# Controller_Sheet.net
KiCad netlist of a schematic drawn in Altium Designer
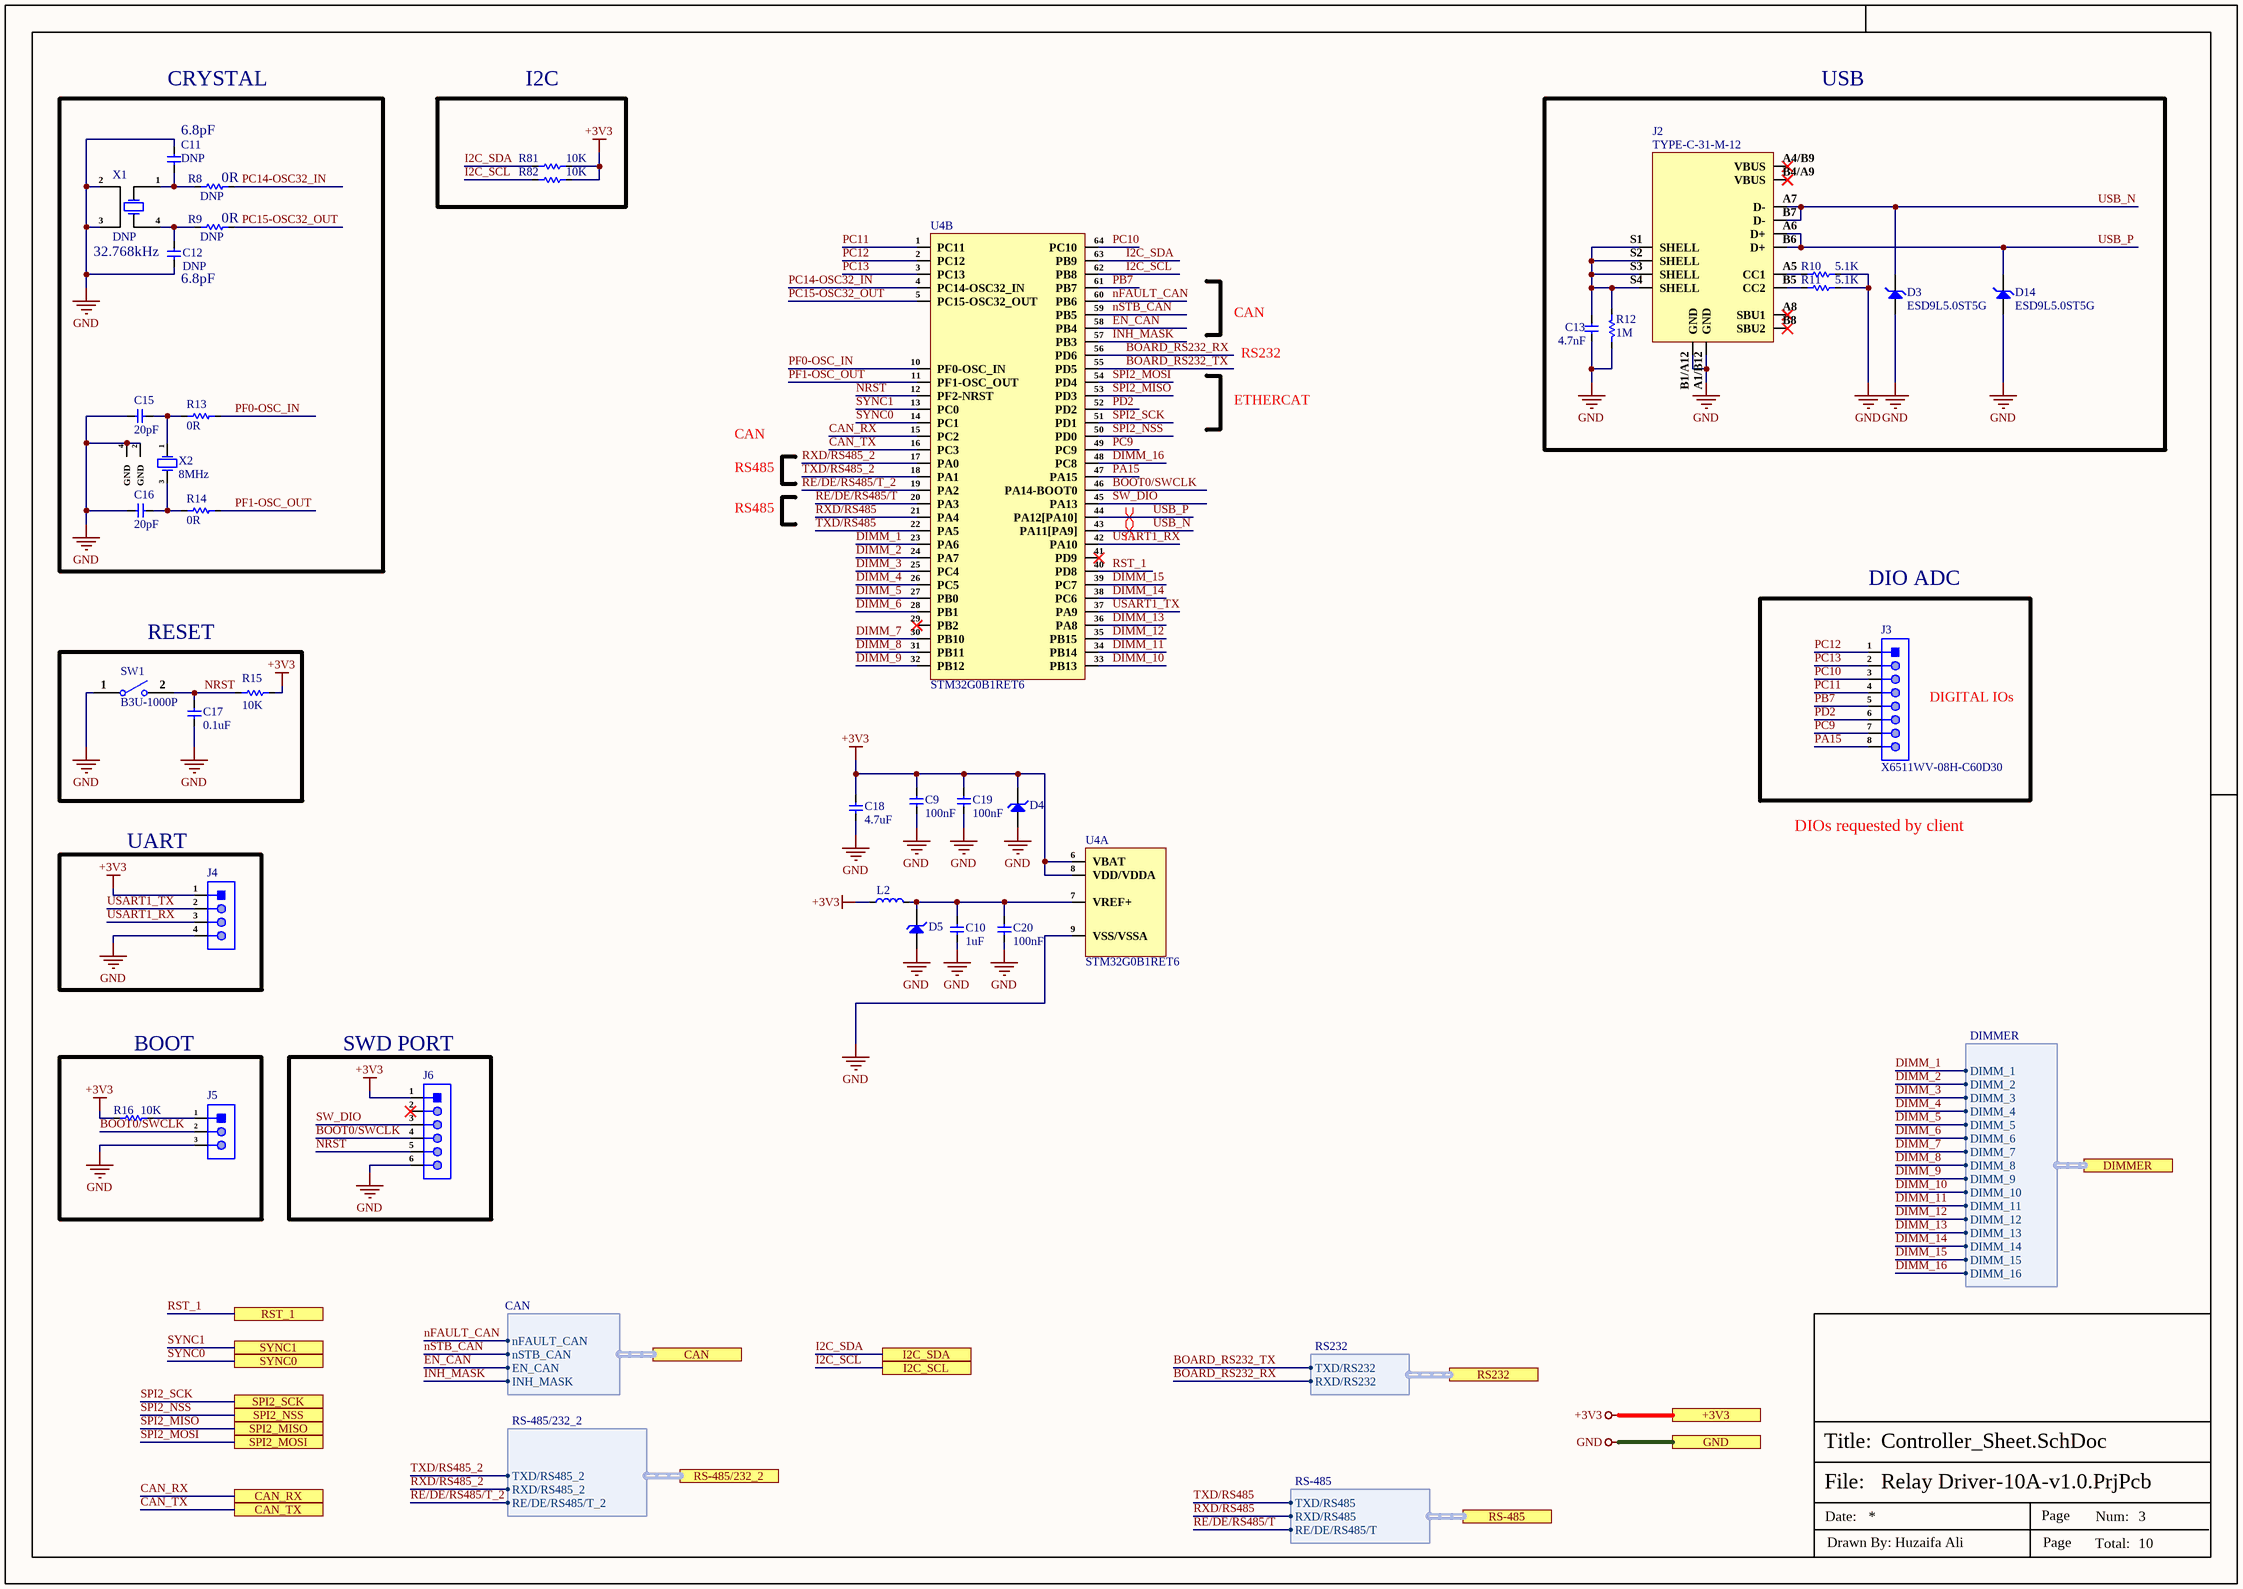
[diagram p0: Controller_Sheet.SchDoc]

(export (version "E")
  (design (tool "Eeschema 10.0.6"))
  (components
    (comp (ref "C9")
      (value "100nF")
      (footprint "cap-0402")
      (description "CAP CER 0.1UF 50V X7R 0402")
      (fields
        (field (name "MANUFACTURER") "TDK")
        (field (name "MANUFACTURER PART NUMBER") "C1005X7R1H104KT000F")
      )
      (libsource (lib "eSpark Libraries") (part "C1005X7R1H104KT000F"))
    )
    (comp (ref "C10")
      (value "1uF")
      (footprint "Cap-0402")
      (description "CAP CER 1UF 10V X5R 0402")
      (fields
        (field (name "MANUFACTURER") "Yageo")
        (field (name "MANUFACTURER PART NUMBER") "CC0402KRX5R6BB105")
      )
      (libsource (lib "eSpark Libraries") (part "CC0402KRX5R6BB105"))
    )
    (comp (ref "C11")
      (value "DNP")
      (footprint "Cap-0402")
      (description "CAP CER 6.8PF 50V C0G/NPO 0402")
      (fields
        (field (name "MANUFACTURER") "Yageo")
        (field (name "MANUFACTURER PART NUMBER") "CC0402CRNPO9BN6R8")
      )
      (libsource (lib "eSpark Libraries") (part "CC0402CRNPO9BN6R8"))
    )
    (comp (ref "C12")
      (value "DNP")
      (footprint "Cap-0402")
      (description "CAP CER 6.8PF 50V C0G/NPO 0402")
      (fields
        (field (name "MANUFACTURER") "Yageo")
        (field (name "MANUFACTURER PART NUMBER") "CC0402CRNPO9BN6R8")
      )
      (libsource (lib "eSpark Libraries") (part "CC0402CRNPO9BN6R8"))
    )
    (comp (ref "C13")
      (value "4.7nF")
      (footprint "Cap-0603")
      (description "CAP CER 4700PF 50V C0G/NPO 0603")
      (fields
        (field (name "MANUFACTURER") "Yageo")
        (field (name "MANUFACTURER PART NUMBER") "CC0603JRNPO9BN472")
      )
      (libsource (lib "eSpark_centralized_Library(2022)") (part "CC0603JRNPO9BN472"))
    )
    (comp (ref "C15")
      (value "20pF")
      (footprint "Cap-0402")
      (description "CAP CER 20PF 50V C0G/NPO 0402")
      (fields (field (name "LCSC PART NUMBER") "C107000") (field (name "MANUFACTURER") "Yageo"))
      (libsource (lib "eSpark Libraries") (part "CC0402JRNPO9BN200"))
    )
    (comp (ref "C16")
      (value "20pF")
      (footprint "Cap-0402")
      (description "CAP CER 20PF 50V C0G/NPO 0402")
      (fields (field (name "LCSC PART NUMBER") "C107000") (field (name "MANUFACTURER") "Yageo"))
      (libsource (lib "eSpark Libraries") (part "CC0402JRNPO9BN200"))
    )
    (comp (ref "C17")
      (value "0.1uF")
      (footprint "Cap-0402")
      (description "CAP CER 0.1UF 16V X7R 0402")
      (fields
        (field (name "MANUFACTURER") "Yageo")
        (field (name "MANUFACTURER PART NUMBER") "CC0402JRX7R7BB104")
      )
      (libsource (lib "eSpark Libraries") (part "CC0402JRX7R7BB104"))
    )
    (comp (ref "C18")
      (value "4.7uF")
      (footprint "Cap-0402")
      (description "CAP CER 4.7UF 10V X5R 0402")
      (fields
        (field (name "MANUFACTURER") "Yageo")
        (field (name "MANUFACTURER PART NUMBER") "CC0402KRX5R6BB475")
      )
      (libsource (lib "eSpark Libraries") (part "CC0402KRX5R6BB475"))
    )
    (comp (ref "C19")
      (value "100nF")
      (footprint "cap-0402")
      (description "CAP CER 0.1UF 50V X7R 0402")
      (fields
        (field (name "MANUFACTURER") "TDK")
        (field (name "MANUFACTURER PART NUMBER") "C1005X7R1H104KT000F")
      )
      (libsource (lib "eSpark Libraries") (part "C1005X7R1H104KT000F"))
    )
    (comp (ref "C20")
      (value "100nF")
      (footprint "cap-0402")
      (description "CAP CER 0.1UF 50V X7R 0402")
      (fields
        (field (name "MANUFACTURER") "TDK")
        (field (name "MANUFACTURER PART NUMBER") "C1005X7R1H104KT000F")
      )
      (libsource (lib "eSpark Libraries") (part "C1005X7R1H104KT000F"))
    )
    (comp (ref "D3")
      (value "ESD9L5.0ST5G")
      (footprint "SOD-923.")
      (description "TVS DIODE 5V 9.8V SOD923")
      (fields (field (name "MANUFACTURER") "ON Semiconductor") (field (name "LCSC PART NUMBER") "C82326"))
      (libsource (lib "eSpark Libraries") (part "ESD9L5.0ST5G"))
    )
    (comp (ref "D4")
      (value "AZ3003-01G")
      (footprint "SOD-123")
      (description "TVS SURGE PROTECTOR 1-CH 3.3V")
      (fields (field (name "MANUFACTURER") "Amazing"))
      (libsource (lib "eSpark Libraries") (part "AZ3003-01G"))
    )
    (comp (ref "D5")
      (value "AZ3003-01G")
      (footprint "SOD-123")
      (description "TVS SURGE PROTECTOR 1-CH 3.3V")
      (fields (field (name "MANUFACTURER") "Amazing"))
      (libsource (lib "eSpark Libraries") (part "AZ3003-01G"))
    )
    (comp (ref "D14")
      (value "ESD9L5.0ST5G")
      (footprint "SOD-923.")
      (description "TVS DIODE 5V 9.8V SOD923")
      (fields (field (name "MANUFACTURER") "ON Semiconductor") (field (name "LCSC PART NUMBER") "C82326"))
      (libsource (lib "eSpark Libraries") (part "ESD9L5.0ST5G"))
    )
    (comp (ref "J2")
      (value "TYPE-C-31-M-12")
      (footprint "TYPE-C-31-M-12_")
      (description "5A 1 16P Female Type-C SMD USB Connectors ROHS")
      (fields
        (field (name "MANUFACTURER") "Korean Hroparts Elec")
        (field (name "LCSC PART NUMBER") "C165948")
      )
      (libsource (lib "eSpark Libraries") (part "TYPE-C-31-M-12"))
    )
    (comp (ref "J3")
      (value "X6511WV-08H-C60D30")
      (footprint "HDR 1x8 TH male")
      (fields (field (name "MANUFACTURER") "XKB") (field (name "LCSC PART NUMBER") "C706880"))
      (libsource (lib "eSpark Libraries") (part "X6511WV-08H-C60D30"))
    )
    (comp (ref "J4")
      (value "X6511WV-04H-C60D30")
      (footprint "HDR1X4_")
      (fields (field (name "MANUFACTURER") "XKB") (field (name "LCSC PART NUMBER") "C706876"))
      (libsource (lib "eSpark Libraries") (part "X6511WV-04H-C60D30"))
    )
    (comp (ref "J5")
      (value "68000-103HLF")
      (footprint "HDR1X3_")
      (description "CONN HEADER VERT 3POS 2.54MM")
      (fields (field (name "LCSC PART NUMBER") "C168677"))
      (libsource (lib "eSpark Libraries") (part "68000-103HLF"))
    )
    (comp (ref "J6")
      (value "X6511WV-06H-C60D30")
      (footprint "HDR1X6_")
      (fields (field (name "MANUFACTURER") "XKB") (field (name "LCSC PART NUMBER") "C706878"))
      (libsource (lib "eSpark Libraries") (part "X6511WV-06H-C60D30"))
    )
    (comp (ref "L2")
      (value "BLM15AG601SN1D")
      (footprint "IND-0402")
      (description "FERRITE BEAD 600 OHM 0402 1LN")
      (fields (field (name "MANUFACTURER") "Murata") (field (name "TOLERANCE") "25%"))
      (libsource (lib "eSpark Libraries") (part "BLM15AG601SN1D"))
    )
    (comp (ref "R8")
      (value "DNP")
      (footprint "Res-0603")
      (description "RES 0 OHM JUMPER 1/10W 0603")
      (fields
        (field (name "MANUFACTURER") "Yageo")
        (field (name "MANUFACTURER PART NUMBER") "RC0603JR-070RL")
      )
      (libsource (lib "eSpark Libraries") (part "RC0603JR-070RL"))
    )
    (comp (ref "R9")
      (value "DNP")
      (footprint "Res-0603")
      (description "RES 0 OHM JUMPER 1/10W 0603")
      (fields
        (field (name "MANUFACTURER") "Yageo")
        (field (name "MANUFACTURER PART NUMBER") "RC0603JR-070RL")
      )
      (libsource (lib "eSpark Libraries") (part "RC0603JR-070RL"))
    )
    (comp (ref "R10")
      (value "5.1K")
      (footprint "Res-0402")
      (description "RES 5.1K OHM 1% 1/16W 0402")
      (fields
        (field (name "MANUFACTURER") "Yageo")
        (field (name "MANUFACTURER PART NUMBER") "RC0402FR-075K1L")
      )
      (libsource (lib "eSpark Libraries") (part "RC0402FR-075K1L"))
    )
    (comp (ref "R11")
      (value "5.1K")
      (footprint "Res-0402")
      (description "RES 5.1K OHM 1% 1/16W 0402")
      (fields
        (field (name "MANUFACTURER") "Yageo")
        (field (name "MANUFACTURER PART NUMBER") "RC0402FR-075K1L")
      )
      (libsource (lib "eSpark Libraries") (part "RC0402FR-075K1L"))
    )
    (comp (ref "R12")
      (value "1M")
      (footprint "Res-0402")
      (description "RES SMD 1M OHM 5% 1/16W 0402")
      (fields
        (field (name "MANUFACTURER") "Yageo")
        (field (name "MANUFACTURER PART NUMBER") "AF0402JR-071ML")
      )
      (libsource (lib "eSpark_centralized_Library(2022)") (part "AF0402JR-071ML"))
    )
    (comp (ref "R13")
      (value "0R")
      (footprint "Res-0603")
      (description "RES 0 OHM JUMPER 1/10W 0603")
      (fields
        (field (name "MANUFACTURER") "Yageo")
        (field (name "MANUFACTURER PART NUMBER") "RC0603JR-070RL")
      )
      (libsource (lib "eSpark Libraries") (part "RC0603JR-070RL"))
    )
    (comp (ref "R14")
      (value "0R")
      (footprint "Res-0603")
      (description "RES 0 OHM JUMPER 1/10W 0603")
      (fields
        (field (name "MANUFACTURER") "Yageo")
        (field (name "MANUFACTURER PART NUMBER") "RC0603JR-070RL")
      )
      (libsource (lib "eSpark Libraries") (part "RC0603JR-070RL"))
    )
    (comp (ref "R15")
      (value "10K")
      (footprint "Res-0402")
      (description "RES 10K OHM 1% 1/16W 0402")
      (fields
        (field (name "MANUFACTURER") "Yageo")
        (field (name "MANUFACTURER PART NUMBER") "RC0402FR-0710KL")
      )
      (libsource (lib "eSpark Libraries") (part "RC0402FR-0710KL"))
    )
    (comp (ref "R16")
      (value "10K")
      (footprint "Res-0402")
      (description "RES 10K OHM 1% 1/16W 0402")
      (fields
        (field (name "MANUFACTURER") "Yageo")
        (field (name "MANUFACTURER PART NUMBER") "RC0402FR-0710KL")
      )
      (libsource (lib "eSpark Libraries") (part "RC0402FR-0710KL"))
    )
    (comp (ref "R81")
      (value "10K")
      (footprint "Res-0402")
      (description "RES 10K OHM 1% 1/16W 0402")
      (fields
        (field (name "MANUFACTURER") "Yageo")
        (field (name "MANUFACTURER PART NUMBER") "RC0402FR-0710KL")
      )
      (libsource (lib "eSpark Libraries") (part "RC0402FR-0710KL"))
    )
    (comp (ref "R82")
      (value "10K")
      (footprint "Res-0402")
      (description "RES 10K OHM 1% 1/16W 0402")
      (fields
        (field (name "MANUFACTURER") "Yageo")
        (field (name "MANUFACTURER PART NUMBER") "RC0402FR-0710KL")
      )
      (libsource (lib "eSpark Libraries") (part "RC0402FR-0710KL"))
    )
    (comp (ref "SW1")
      (value "B3U-1000P")
      (footprint "B3U-1000P")
      (description "SWITCH TACTILE SPST-NO 0.05A 12V")
      (fields (field (name "MANUFACTURER") "Omron") (field (name "LCSC PART NUMBER") "C231329"))
      (libsource (lib "eSpark Libraries") (part "B3U-1000P"))
    )
    (comp (ref "U4")
      (value "STM32G0B1RET6")
      (footprint "LQFP-64(10x10)")
      (description "IC MCU 32BIT 512KB FLASH 64LQFP")
      (fields (field (name "MANUFACTURER") "STMicroelectronics") (field (name "LCSC PART NUMBER") "C2829307"))
      (libsource (lib "eSpark Libraries") (part "STM32G0B1RET6"))
    )
    (comp (ref "X1")
      (value "DNP")
      (footprint "MC-306")
      (description "32.768kHz 12.5pF ±20ppm MC-306 Crystals ROHS")
      (fields
        (field (name "MANUFACTURER") "Seiko Epson")
        (field (name "MANUFACTURER PART NUMBER") "MC-306 32.7680K-A0:ROHS")
      )
      (libsource (lib "eSpark Libraries") (part "MC-306 32.7680K-A0{colon}ROHS"))
    )
    (comp (ref "X2")
      (value "8MHz")
      (footprint "5TJ480000XYLBC_")
      (description "8MHz 18pF ±10ppm SMD5032-4P Crystals ROHS")
      (fields (field (name "MANUFACTURER") "JYJE") (field (name "MANUFACTURER PART NUMBER") "5TJ480000XYLBC"))
      (libsource (lib "eSpark Libraries") (part "5TJ480000XYLBC"))
    )
  )
  (nets
    (net (code "6") (name "+3V3") (class "Default")
      (node (ref "C18") (pin "2") (pinfunction "2_2") (pintype "passive"))
      (node (ref "C19") (pin "2") (pinfunction "2_2") (pintype "passive"))
      (node (ref "C9") (pin "2") (pinfunction "2_2") (pintype "passive"))
      (node (ref "D4") (pin "2") (pinfunction "K_2") (pintype "passive"))
      (node (ref "J4") (pin "1") (pinfunction "1_1") (pintype "passive"))
      (node (ref "J6") (pin "1") (pinfunction "1_1") (pintype "passive"))
      (node (ref "L2") (pin "1") (pinfunction "1_1") (pintype "passive"))
      (node (ref "R15") (pin "2") (pinfunction "2_2") (pintype "passive"))
      (node (ref "R16") (pin "2") (pinfunction "2_2") (pintype "passive"))
      (node (ref "R81") (pin "2") (pinfunction "2_2") (pintype "passive"))
      (node (ref "R82") (pin "2") (pinfunction "2_2") (pintype "passive"))
      (node (ref "U4") (pin "6") (pinfunction "VBAT_6") (pintype "passive"))
      (node (ref "U4") (pin "8") (pinfunction "VDD/VDDA_8") (pintype "passive"))
    )
    (net (code "7") (name "/BOARD_RS232_RX") (class "Default")
      (node (ref "U4") (pin "56") (pinfunction "PD6_56") (pintype "passive"))
    )
    (net (code "8") (name "/BOARD_RS232_TX") (class "Default")
      (node (ref "U4") (pin "55") (pinfunction "PD5_55") (pintype "passive"))
    )
    (net (code "9") (name "/BOOT0{slash}SWCLK") (class "Default")
      (node (ref "J5") (pin "2") (pinfunction "2_2") (pintype "passive"))
      (node (ref "J6") (pin "4") (pinfunction "4_4") (pintype "passive"))
      (node (ref "U4") (pin "46") (pinfunction "PA14-BOOT0_46") (pintype "passive"))
    )
    (net (code "10") (name "/CAN_RX") (class "Default")
      (node (ref "U4") (pin "15") (pinfunction "PC2_15") (pintype "passive"))
    )
    (net (code "11") (name "/CAN_TX") (class "Default")
      (node (ref "U4") (pin "16") (pinfunction "PC3_16") (pintype "passive"))
    )
    (net (code "12") (name "/DIMM_1") (class "Default")
      (node (ref "U4") (pin "23") (pinfunction "PA6_23") (pintype "passive"))
    )
    (net (code "13") (name "/DIMM_2") (class "Default")
      (node (ref "U4") (pin "24") (pinfunction "PA7_24") (pintype "passive"))
    )
    (net (code "14") (name "/DIMM_3") (class "Default")
      (node (ref "U4") (pin "25") (pinfunction "PC4_25") (pintype "passive"))
    )
    (net (code "15") (name "/DIMM_4") (class "Default")
      (node (ref "U4") (pin "26") (pinfunction "PC5_26") (pintype "passive"))
    )
    (net (code "16") (name "/DIMM_5") (class "Default")
      (node (ref "U4") (pin "27") (pinfunction "PB0_27") (pintype "passive"))
    )
    (net (code "17") (name "/DIMM_6") (class "Default")
      (node (ref "U4") (pin "28") (pinfunction "PB1_28") (pintype "passive"))
    )
    (net (code "18") (name "/DIMM_7") (class "Default")
      (node (ref "U4") (pin "30") (pinfunction "PB10_30") (pintype "passive"))
    )
    (net (code "19") (name "/DIMM_8") (class "Default")
      (node (ref "U4") (pin "31") (pinfunction "PB11_31") (pintype "passive"))
    )
    (net (code "20") (name "/DIMM_9") (class "Default")
      (node (ref "U4") (pin "32") (pinfunction "PB12_32") (pintype "passive"))
    )
    (net (code "21") (name "/DIMM_10") (class "Default")
      (node (ref "U4") (pin "33") (pinfunction "PB13_33") (pintype "passive"))
    )
    (net (code "22") (name "/DIMM_11") (class "Default")
      (node (ref "U4") (pin "34") (pinfunction "PB14_34") (pintype "passive"))
    )
    (net (code "23") (name "/DIMM_12") (class "Default")
      (node (ref "U4") (pin "35") (pinfunction "PB15_35") (pintype "passive"))
    )
    (net (code "24") (name "/DIMM_13") (class "Default")
      (node (ref "U4") (pin "36") (pinfunction "PA8_36") (pintype "passive"))
    )
    (net (code "25") (name "/DIMM_14") (class "Default")
      (node (ref "U4") (pin "38") (pinfunction "PC6_38") (pintype "passive"))
    )
    (net (code "26") (name "/DIMM_15") (class "Default")
      (node (ref "U4") (pin "39") (pinfunction "PC7_39") (pintype "passive"))
    )
    (net (code "27") (name "/DIMM_16") (class "Default")
      (node (ref "U4") (pin "48") (pinfunction "PC8_48") (pintype "passive"))
    )
    (net (code "28") (name "/EN_CAN") (class "Default")
      (node (ref "U4") (pin "58") (pinfunction "PB4_58") (pintype "passive"))
    )
    (net (code "29") (name "/I2C_SCL") (class "Default")
      (node (ref "R82") (pin "1") (pinfunction "1_1") (pintype "passive"))
      (node (ref "U4") (pin "62") (pinfunction "PB8_62") (pintype "passive"))
    )
    (net (code "30") (name "/I2C_SDA") (class "Default")
      (node (ref "R81") (pin "1") (pinfunction "1_1") (pintype "passive"))
      (node (ref "U4") (pin "63") (pinfunction "PB9_63") (pintype "passive"))
    )
    (net (code "31") (name "/INH_MASK") (class "Default")
      (node (ref "U4") (pin "57") (pinfunction "PB3_57") (pintype "passive"))
    )
    (net (code "32") (name "/NRST") (class "Default")
      (node (ref "C17") (pin "2") (pinfunction "2_2") (pintype "passive"))
      (node (ref "J6") (pin "5") (pinfunction "5_5") (pintype "passive"))
      (node (ref "R15") (pin "1") (pinfunction "1_1") (pintype "passive"))
      (node (ref "SW1") (pin "2") (pinfunction "2_2") (pintype "passive"))
      (node (ref "U4") (pin "12") (pinfunction "PF2-NRST_12") (pintype "passive"))
    )
    (net (code "33") (name "/PA15") (class "Default")
      (node (ref "J3") (pin "8") (pinfunction "8_8") (pintype "passive"))
      (node (ref "U4") (pin "47") (pinfunction "PA15_47") (pintype "passive"))
    )
    (net (code "34") (name "/PB7") (class "Default")
      (node (ref "J3") (pin "5") (pinfunction "5_5") (pintype "passive"))
      (node (ref "U4") (pin "61") (pinfunction "PB7_61") (pintype "passive"))
    )
    (net (code "35") (name "/PC9") (class "Default")
      (node (ref "J3") (pin "7") (pinfunction "7_7") (pintype "passive"))
      (node (ref "U4") (pin "49") (pinfunction "PC9_49") (pintype "passive"))
    )
    (net (code "36") (name "/PC10") (class "Default")
      (node (ref "J3") (pin "3") (pinfunction "3_3") (pintype "passive"))
      (node (ref "U4") (pin "64") (pinfunction "PC10_64") (pintype "passive"))
    )
    (net (code "37") (name "/PC11") (class "Default")
      (node (ref "J3") (pin "4") (pinfunction "4_4") (pintype "passive"))
      (node (ref "U4") (pin "1") (pinfunction "PC11_1") (pintype "passive"))
    )
    (net (code "38") (name "/PC12") (class "Default")
      (node (ref "J3") (pin "1") (pinfunction "1_1") (pintype "passive"))
      (node (ref "U4") (pin "2") (pinfunction "PC12_2") (pintype "passive"))
    )
    (net (code "39") (name "/PC13") (class "Default")
      (node (ref "J3") (pin "2") (pinfunction "2_2") (pintype "passive"))
      (node (ref "U4") (pin "3") (pinfunction "PC13_3") (pintype "passive"))
    )
    (net (code "40") (name "/PC14-OSC32_IN") (class "Default")
      (node (ref "R8") (pin "2") (pinfunction "2_2") (pintype "passive"))
      (node (ref "U4") (pin "4") (pinfunction "PC14-OSC32_IN_4") (pintype "passive"))
    )
    (net (code "41") (name "/PC15-OSC32_OUT") (class "Default")
      (node (ref "R9") (pin "2") (pinfunction "2_2") (pintype "passive"))
      (node (ref "U4") (pin "5") (pinfunction "PC15-OSC32_OUT_5") (pintype "passive"))
    )
    (net (code "42") (name "/PD2") (class "Default")
      (node (ref "J3") (pin "6") (pinfunction "6_6") (pintype "passive"))
      (node (ref "U4") (pin "52") (pinfunction "PD2_52") (pintype "passive"))
    )
    (net (code "43") (name "/PF0-OSC_IN") (class "Default")
      (node (ref "R13") (pin "2") (pinfunction "2_2") (pintype "passive"))
      (node (ref "U4") (pin "10") (pinfunction "PF0-OSC_IN_10") (pintype "passive"))
    )
    (net (code "44") (name "/PF1-OSC_OUT") (class "Default")
      (node (ref "R14") (pin "2") (pinfunction "2_2") (pintype "passive"))
      (node (ref "U4") (pin "11") (pinfunction "PF1-OSC_OUT_11") (pintype "passive"))
    )
    (net (code "45") (name "/RE{slash}DE{slash}RS485{slash}T") (class "Default")
      (node (ref "U4") (pin "20") (pinfunction "PA3_20") (pintype "passive"))
    )
    (net (code "46") (name "/RE{slash}DE{slash}RS485{slash}T_2") (class "Default")
      (node (ref "U4") (pin "19") (pinfunction "PA2_19") (pintype "passive"))
    )
    (net (code "47") (name "/RST_1") (class "Default")
      (node (ref "U4") (pin "40") (pinfunction "PD8_40") (pintype "passive"))
    )
    (net (code "48") (name "/RXD{slash}RS485") (class "Default")
      (node (ref "U4") (pin "21") (pinfunction "PA4_21") (pintype "passive"))
    )
    (net (code "49") (name "/RXD{slash}RS485_2") (class "Default")
      (node (ref "U4") (pin "17") (pinfunction "PA0_17") (pintype "passive"))
    )
    (net (code "50") (name "/SPI2_MISO") (class "Default")
      (node (ref "U4") (pin "53") (pinfunction "PD3_53") (pintype "passive"))
    )
    (net (code "51") (name "/SPI2_MOSI") (class "Default")
      (node (ref "U4") (pin "54") (pinfunction "PD4_54") (pintype "passive"))
    )
    (net (code "52") (name "/SPI2_NSS") (class "Default")
      (node (ref "U4") (pin "50") (pinfunction "PD0_50") (pintype "passive"))
    )
    (net (code "53") (name "/SPI2_SCK") (class "Default")
      (node (ref "U4") (pin "51") (pinfunction "PD1_51") (pintype "passive"))
    )
    (net (code "54") (name "/SW_DIO") (class "Default")
      (node (ref "J6") (pin "3") (pinfunction "3_3") (pintype "passive"))
      (node (ref "U4") (pin "45") (pinfunction "PA13_45") (pintype "passive"))
    )
    (net (code "55") (name "/SYNC0") (class "Default")
      (node (ref "U4") (pin "14") (pinfunction "PC1_14") (pintype "passive"))
    )
    (net (code "56") (name "/SYNC1") (class "Default")
      (node (ref "U4") (pin "13") (pinfunction "PC0_13") (pintype "passive"))
    )
    (net (code "57") (name "/TXD{slash}RS485") (class "Default")
      (node (ref "U4") (pin "22") (pinfunction "PA5_22") (pintype "passive"))
    )
    (net (code "58") (name "/TXD{slash}RS485_2") (class "Default")
      (node (ref "U4") (pin "18") (pinfunction "PA1_18") (pintype "passive"))
    )
    (net (code "59") (name "/USART1_RX") (class "Default")
      (node (ref "J4") (pin "3") (pinfunction "3_3") (pintype "passive"))
      (node (ref "U4") (pin "42") (pinfunction "PA10_42") (pintype "passive"))
    )
    (net (code "60") (name "/USART1_TX") (class "Default")
      (node (ref "J4") (pin "2") (pinfunction "2_2") (pintype "passive"))
      (node (ref "U4") (pin "37") (pinfunction "PA9_37") (pintype "passive"))
    )
    (net (code "61") (name "/USB_N") (class "Default")
      (node (ref "D3") (pin "1") (pinfunction "K_1") (pintype "passive"))
      (node (ref "J2") (pin "A7") (pinfunction "D-_A7") (pintype "passive"))
      (node (ref "J2") (pin "B7") (pinfunction "D-_B7") (pintype "passive"))
      (node (ref "U4") (pin "43") (pinfunction "PA11[PA9]_43") (pintype "passive"))
    )
    (net (code "62") (name "/USB_P") (class "Default")
      (node (ref "D14") (pin "1") (pinfunction "K_1") (pintype "passive"))
      (node (ref "J2") (pin "A6") (pinfunction "D+_A6") (pintype "passive"))
      (node (ref "J2") (pin "B6") (pinfunction "D+_B6") (pintype "passive"))
      (node (ref "U4") (pin "44") (pinfunction "PA12[PA10]_44") (pintype "passive"))
    )
    (net (code "63") (name "/nFAULT_CAN") (class "Default")
      (node (ref "U4") (pin "60") (pinfunction "PB6_60") (pintype "passive"))
    )
    (net (code "64") (name "/nSTB_CAN") (class "Default")
      (node (ref "U4") (pin "59") (pinfunction "PB5_59") (pintype "passive"))
    )
    (net (code "70") (name "GND") (class "Default")
      (node (ref "C10") (pin "1") (pinfunction "1_1") (pintype "passive"))
      (node (ref "C11") (pin "1") (pinfunction "1_1") (pintype "passive"))
      (node (ref "C12") (pin "2") (pinfunction "2_2") (pintype "passive"))
      (node (ref "C13") (pin "1") (pinfunction "1_1") (pintype "passive"))
      (node (ref "C15") (pin "1") (pinfunction "1_1") (pintype "passive"))
      (node (ref "C16") (pin "2") (pinfunction "2_2") (pintype "passive"))
      (node (ref "C17") (pin "1") (pinfunction "1_1") (pintype "passive"))
      (node (ref "C18") (pin "1") (pinfunction "1_1") (pintype "passive"))
      (node (ref "C19") (pin "1") (pinfunction "1_1") (pintype "passive"))
      (node (ref "C20") (pin "1") (pinfunction "1_1") (pintype "passive"))
      (node (ref "C9") (pin "1") (pinfunction "1_1") (pintype "passive"))
      (node (ref "D14") (pin "2") (pinfunction "A_2") (pintype "passive"))
      (node (ref "D3") (pin "2") (pinfunction "A_2") (pintype "passive"))
      (node (ref "D4") (pin "1") (pinfunction "A_1") (pintype "passive"))
      (node (ref "D5") (pin "1") (pinfunction "A_1") (pintype "passive"))
      (node (ref "J2") (pin "A1/B12") (pinfunction "GND_A1/B12") (pintype "power_in"))
      (node (ref "J2") (pin "B1/A12") (pinfunction "GND_B1/A12") (pintype "power_in"))
      (node (ref "J4") (pin "4") (pinfunction "4_4") (pintype "passive"))
      (node (ref "J5") (pin "3") (pinfunction "3_3") (pintype "passive"))
      (node (ref "J6") (pin "6") (pinfunction "6_6") (pintype "passive"))
      (node (ref "R10") (pin "2") (pinfunction "2_2") (pintype "passive"))
      (node (ref "R11") (pin "2") (pinfunction "2_2") (pintype "passive"))
      (node (ref "R12") (pin "2") (pinfunction "2_2") (pintype "passive"))
      (node (ref "SW1") (pin "1") (pinfunction "1_1") (pintype "passive"))
      (node (ref "U4") (pin "9") (pinfunction "VSS/VSSA_9") (pintype "passive"))
      (node (ref "X1") (pin "2") (pinfunction "2_2") (pintype "passive"))
      (node (ref "X1") (pin "3") (pinfunction "3_3") (pintype "passive"))
      (node (ref "X2") (pin "2") (pinfunction "GND_2") (pintype "passive"))
      (node (ref "X2") (pin "4") (pinfunction "GND_4") (pintype "passive"))
    )
    (net (code "71") (name "Net-(C13-Pad2)") (class "Default")
      (node (ref "C13") (pin "2") (pinfunction "2_2") (pintype "passive"))
      (node (ref "J2") (pin "S1") (pinfunction "SHELL_S1") (pintype "passive"))
      (node (ref "J2") (pin "S2") (pinfunction "SHELL_S2") (pintype "passive"))
      (node (ref "J2") (pin "S3") (pinfunction "SHELL_S3") (pintype "passive"))
      (node (ref "J2") (pin "S4") (pinfunction "SHELL_S4") (pintype "passive"))
      (node (ref "R12") (pin "1") (pinfunction "1_1") (pintype "passive"))
    )
    (net (code "72") (name "Net-(D5-K)") (class "Default")
      (node (ref "C10") (pin "2") (pinfunction "2_2") (pintype "passive"))
      (node (ref "C20") (pin "2") (pinfunction "2_2") (pintype "passive"))
      (node (ref "D5") (pin "2") (pinfunction "K_2") (pintype "passive"))
      (node (ref "L2") (pin "2") (pinfunction "2_2") (pintype "passive"))
      (node (ref "U4") (pin "7") (pinfunction "VREF+_7") (pintype "passive"))
    )
    (net (code "73") (name "Net-(J2-CC1)") (class "Default")
      (node (ref "J2") (pin "A5") (pinfunction "CC1_A5") (pintype "passive"))
      (node (ref "R10") (pin "1") (pinfunction "1_1") (pintype "passive"))
    )
    (net (code "74") (name "Net-(J2-CC2)") (class "Default")
      (node (ref "J2") (pin "B5") (pinfunction "CC2_B5") (pintype "passive"))
      (node (ref "R11") (pin "1") (pinfunction "1_1") (pintype "passive"))
    )
    (net (code "75") (name "Net-(J5-Pad1)") (class "Default")
      (node (ref "J5") (pin "1") (pinfunction "1_1") (pintype "passive"))
      (node (ref "R16") (pin "1") (pinfunction "1_1") (pintype "passive"))
    )
    (net (code "76") (name "Net-(X1-OSC1)") (class "Default")
      (node (ref "C11") (pin "2") (pinfunction "2_2") (pintype "passive"))
      (node (ref "R8") (pin "1") (pinfunction "1_1") (pintype "passive"))
      (node (ref "X1") (pin "1") (pinfunction "OSC1_1") (pintype "passive"))
    )
    (net (code "77") (name "Net-(X1-OSC2)") (class "Default")
      (node (ref "C12") (pin "1") (pinfunction "1_1") (pintype "passive"))
      (node (ref "R9") (pin "1") (pinfunction "1_1") (pintype "passive"))
      (node (ref "X1") (pin "4") (pinfunction "OSC2_4") (pintype "passive"))
    )
    (net (code "78") (name "Net-(X2-OSC1)") (class "Default")
      (node (ref "C15") (pin "2") (pinfunction "2_2") (pintype "passive"))
      (node (ref "R13") (pin "1") (pinfunction "1_1") (pintype "passive"))
      (node (ref "X2") (pin "1") (pinfunction "OSC1_1") (pintype "passive"))
    )
    (net (code "79") (name "Net-(X2-OSC2)") (class "Default")
      (node (ref "C16") (pin "1") (pinfunction "1_1") (pintype "passive"))
      (node (ref "R14") (pin "1") (pinfunction "1_1") (pintype "passive"))
      (node (ref "X2") (pin "3") (pinfunction "OSC2_3") (pintype "passive"))
    )
    (net (code "80") (name "unconnected-(J2-SBU1-PadA8)") (class "Default")
      (node (ref "J2") (pin "A8") (pinfunction "SBU1_A8") (pintype "passive+no_connect"))
    )
    (net (code "81") (name "unconnected-(J2-SBU2-PadB8)") (class "Default")
      (node (ref "J2") (pin "B8") (pinfunction "SBU2_B8") (pintype "passive+no_connect"))
    )
    (net (code "82") (name "unconnected-(J2-VBUS-PadA4{slash}B9)") (class "Default")
      (node (ref "J2") (pin "A4/B9") (pinfunction "VBUS_A4/B9") (pintype "power_in+no_connect"))
    )
    (net (code "83") (name "unconnected-(J2-VBUS-PadB4{slash}A9)") (class "Default")
      (node (ref "J2") (pin "B4/A9") (pinfunction "VBUS_B4/A9") (pintype "power_in+no_connect"))
    )
    (net (code "84") (name "unconnected-(J6-Pad2)") (class "Default")
      (node (ref "J6") (pin "2") (pinfunction "2_2") (pintype "passive+no_connect"))
    )
    (net (code "85") (name "unconnected-(U4B-PB2-Pad29)") (class "Default")
      (node (ref "U4") (pin "29") (pinfunction "PB2_29") (pintype "passive+no_connect"))
    )
    (net (code "86") (name "unconnected-(U4B-PD9-Pad41)") (class "Default")
      (node (ref "U4") (pin "41") (pinfunction "PD9_41") (pintype "passive+no_connect"))
    )
  )
)
